# M_E_ext_sensor.net
KiCad netlist of a schematic drawn in EAGLE
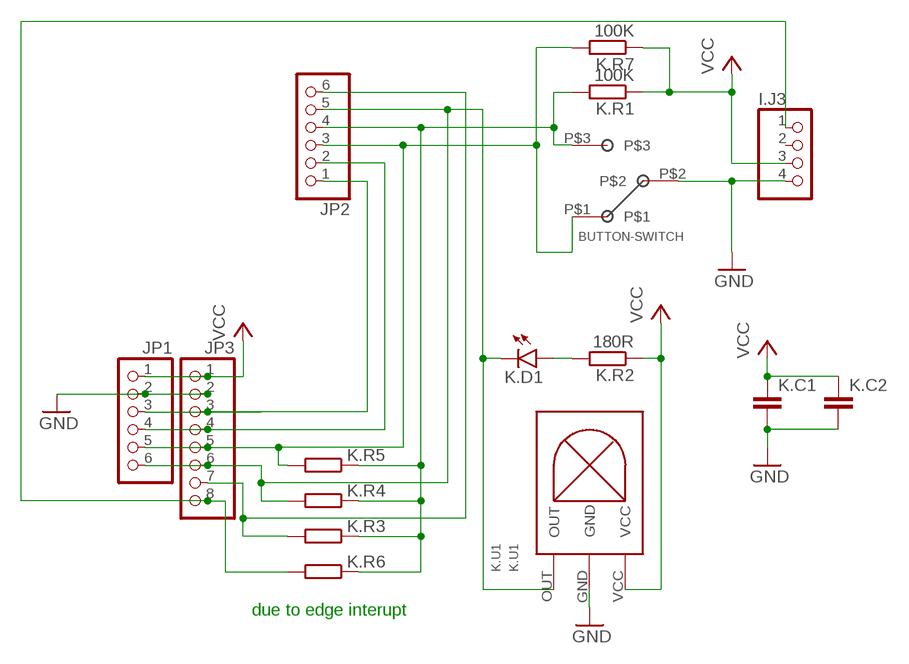
[diagram p0: schematic, sheet 1]

(export (version "E")
  (design (tool "Eeschema 10.0.6"))
  (components
    (comp (ref "I.J3")
      (value "PINHD-1X4")
      (footprint "eagle-import:1X04")
      (libsource (lib "eagle-import") (part "PINHD-1X4"))
    )
    (comp (ref "JP1")
      (value "PINHD-1X6")
      (footprint "eagle-import:1X06")
      (libsource (lib "eagle-import") (part "PINHD-1X6"))
    )
    (comp (ref "JP2")
      (value "PINHD-1X6")
      (footprint "eagle-import:1X06")
      (libsource (lib "eagle-import") (part "PINHD-1X6"))
    )
    (comp (ref "JP3")
      (value "PINHD-1X8")
      (footprint "eagle-import:1X08")
      (libsource (lib "eagle-import") (part "PINHD-1X8"))
    )
    (comp (ref "K.C1")
      (value "C-EUC0603")
      (footprint "eagle-import:C0603")
      (libsource (lib "eagle-import") (part "C-EUC0603"))
    )
    (comp (ref "K.C2")
      (value "C-EUC0603")
      (footprint "eagle-import:C0603")
      (libsource (lib "eagle-import") (part "C-EUC0603"))
    )
    (comp (ref "K.D1")
      (value "LEDCHIP-LED0603")
      (footprint "eagle-import:CHIP-LED0603")
      (libsource (lib "eagle-import") (part "LEDCHIP-LED0603"))
    )
    (comp (ref "K.R1")
      (value "100K")
      (footprint "eagle-import:R0603")
      (libsource (lib "eagle-import") (part "R-EU_R0603"))
    )
    (comp (ref "K.R2")
      (value "180R")
      (footprint "eagle-import:R0603")
      (libsource (lib "eagle-import") (part "R-EU_R0603"))
    )
    (comp (ref "K.R3")
      (value "0R")
      (footprint "eagle-import:R0603")
      (libsource (lib "eagle-import") (part "R-EU_R0603"))
    )
    (comp (ref "K.R4")
      (value "0R")
      (footprint "eagle-import:R0603")
      (libsource (lib "eagle-import") (part "R-EU_R0603"))
    )
    (comp (ref "K.R5")
      (value "0R")
      (footprint "eagle-import:R0603")
      (libsource (lib "eagle-import") (part "R-EU_R0603"))
    )
    (comp (ref "K.R6")
      (value "0R")
      (footprint "eagle-import:R0603")
      (libsource (lib "eagle-import") (part "R-EU_R0603"))
    )
    (comp (ref "K.R7")
      (value "100K")
      (footprint "eagle-import:R0603")
      (libsource (lib "eagle-import") (part "R-EU_R0603"))
    )
    (comp (ref "K.U1")
      (value "VS1838B")
      (footprint "eagle-import:IR_RECEIVER")
      (libsource (lib "eagle-import") (part "VS1838B"))
    )
    (comp (ref "U$2")
      (value "BUTTON-SWITCH")
      (footprint "eagle-import:BUTTON-SWITCH")
      (libsource (lib "eagle-import") (part "BUTTON-SWITCH"))
    )
  )
  (nets
    (net (code "1") (name "GND") (class "Default")
      (node (ref "I.J3") (pin "4") (pinfunction "4_4") (pintype "passive"))
      (node (ref "JP1") (pin "2") (pinfunction "2_2") (pintype "passive"))
      (node (ref "JP3") (pin "2") (pinfunction "2_2") (pintype "passive"))
      (node (ref "K.C1") (pin "2") (pinfunction "2_2") (pintype "passive"))
      (node (ref "K.C2") (pin "2") (pinfunction "2_2") (pintype "passive"))
      (node (ref "K.U1") (pin "GND") (pinfunction "GND_GND") (pintype "bidirectional"))
      (node (ref "U$2") (pin "P$2") (pinfunction "P$2_P$2") (pintype "bidirectional"))
    )
    (net (code "2") (name "Net-(I.J3-Pad1)") (class "Default")
      (node (ref "I.J3") (pin "1") (pinfunction "1_1") (pintype "passive"))
      (node (ref "JP3") (pin "8") (pinfunction "8_8") (pintype "passive"))
      (node (ref "K.R6") (pin "2") (pinfunction "2_2") (pintype "passive"))
    )
    (net (code "3") (name "Net-(JP1-Pad3)") (class "Default")
      (node (ref "JP1") (pin "3") (pinfunction "3_3") (pintype "passive"))
      (node (ref "JP2") (pin "1") (pinfunction "1_1") (pintype "passive"))
      (node (ref "JP3") (pin "3") (pinfunction "3_3") (pintype "passive"))
    )
    (net (code "4") (name "Net-(JP1-Pad4)") (class "Default")
      (node (ref "JP1") (pin "4") (pinfunction "4_4") (pintype "passive"))
      (node (ref "JP2") (pin "2") (pinfunction "2_2") (pintype "passive"))
      (node (ref "JP3") (pin "4") (pinfunction "4_4") (pintype "passive"))
    )
    (net (code "5") (name "Net-(JP1-Pad5)") (class "Default")
      (node (ref "JP1") (pin "5") (pinfunction "5_5") (pintype "passive"))
      (node (ref "JP2") (pin "3") (pinfunction "3_3") (pintype "passive"))
      (node (ref "JP3") (pin "5") (pinfunction "5_5") (pintype "passive"))
      (node (ref "K.R5") (pin "2") (pinfunction "2_2") (pintype "passive"))
      (node (ref "K.R7") (pin "2") (pinfunction "2_2") (pintype "passive"))
      (node (ref "U$2") (pin "P$1") (pinfunction "P$1_P$1") (pintype "bidirectional"))
    )
    (net (code "6") (name "Net-(JP2-Pad4)") (class "Default")
      (node (ref "JP2") (pin "4") (pinfunction "4_4") (pintype "passive"))
      (node (ref "K.R1") (pin "2") (pinfunction "2_2") (pintype "passive"))
      (node (ref "K.R3") (pin "1") (pinfunction "1_1") (pintype "passive"))
      (node (ref "K.R4") (pin "1") (pinfunction "1_1") (pintype "passive"))
      (node (ref "K.R5") (pin "1") (pinfunction "1_1") (pintype "passive"))
      (node (ref "K.R6") (pin "1") (pinfunction "1_1") (pintype "passive"))
      (node (ref "U$2") (pin "P$3") (pinfunction "P$3_P$3") (pintype "bidirectional"))
    )
    (net (code "7") (name "Net-(JP2-Pad6)") (class "Default")
      (node (ref "JP2") (pin "6") (pinfunction "6_6") (pintype "passive"))
      (node (ref "JP3") (pin "7") (pinfunction "7_7") (pintype "passive"))
      (node (ref "K.R3") (pin "2") (pinfunction "2_2") (pintype "passive"))
    )
    (net (code "8") (name "Net-(K.D1-A)") (class "Default")
      (node (ref "K.D1") (pin "A1") (pinfunction "A_A1") (pintype "passive"))
      (node (ref "K.R2") (pin "2") (pinfunction "2_2") (pintype "passive"))
    )
    (net (code "9") (name "Net-(K.D1-C)") (class "Default")
      (node (ref "JP1") (pin "6") (pinfunction "6_6") (pintype "passive"))
      (node (ref "JP2") (pin "5") (pinfunction "5_5") (pintype "passive"))
      (node (ref "JP3") (pin "6") (pinfunction "6_6") (pintype "passive"))
      (node (ref "K.D1") (pin "C1") (pinfunction "C_C1") (pintype "passive"))
      (node (ref "K.R4") (pin "2") (pinfunction "2_2") (pintype "passive"))
      (node (ref "K.U1") (pin "OUT") (pinfunction "OUT_OUT") (pintype "bidirectional"))
    )
    (net (code "10") (name "VCC") (class "Default")
      (node (ref "I.J3") (pin "3") (pinfunction "3_3") (pintype "passive"))
      (node (ref "JP1") (pin "1") (pinfunction "1_1") (pintype "passive"))
      (node (ref "JP3") (pin "1") (pinfunction "1_1") (pintype "passive"))
      (node (ref "K.C1") (pin "1") (pinfunction "1_1") (pintype "passive"))
      (node (ref "K.C2") (pin "1") (pinfunction "1_1") (pintype "passive"))
      (node (ref "K.R1") (pin "1") (pinfunction "1_1") (pintype "passive"))
      (node (ref "K.R2") (pin "1") (pinfunction "1_1") (pintype "passive"))
      (node (ref "K.R7") (pin "1") (pinfunction "1_1") (pintype "passive"))
      (node (ref "K.U1") (pin "VCC") (pinfunction "VCC_VCC") (pintype "bidirectional"))
    )
    (net (code "11") (name "unconnected-(I.J3-Pad2)") (class "Default")
      (node (ref "I.J3") (pin "2") (pinfunction "2_2") (pintype "passive"))
    )
  )
)
